# Pack_Disconnect_MOSFETs.net
KiCad netlist of a schematic drawn in Altium Designer
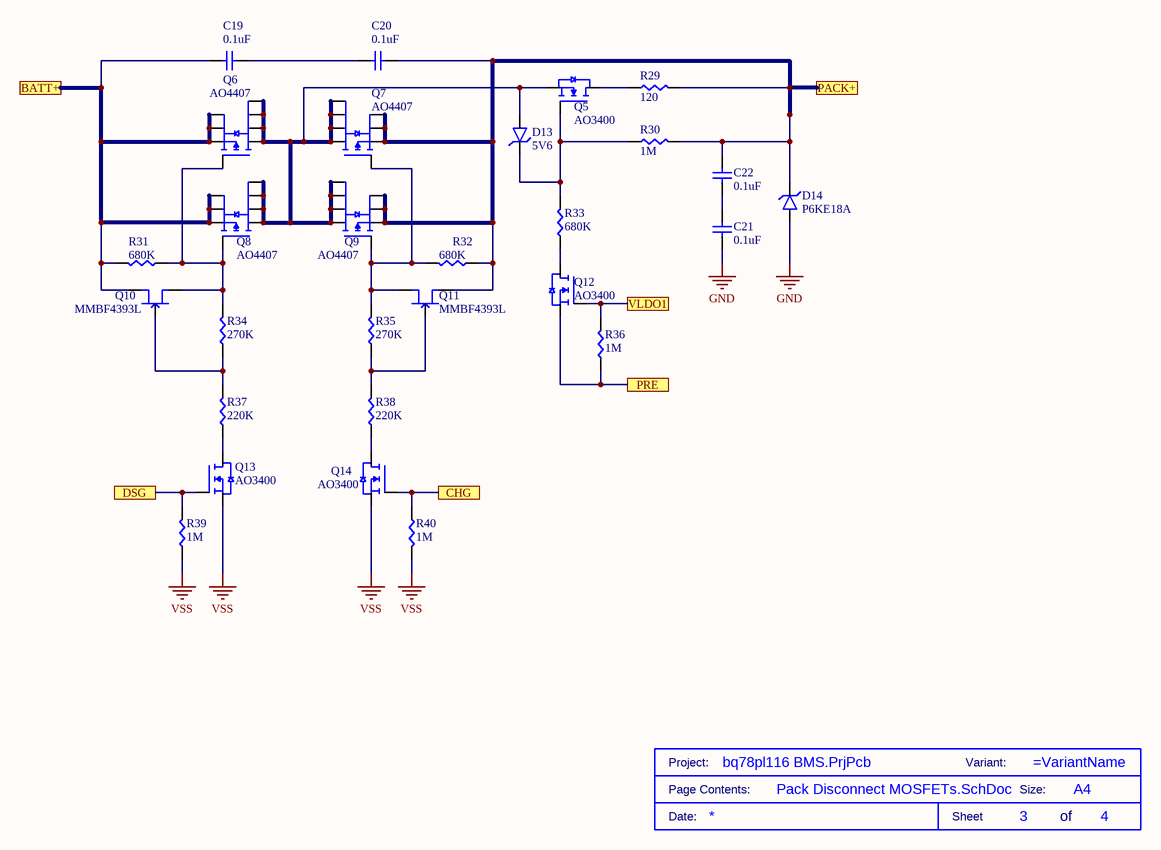
[diagram p0: Pack Disconnect MOSFETs.SchDoc]

(export (version "E")
  (design (tool "Eeschema 10.0.6"))
  (components
    (comp (ref "C19")
      (value "0.1uF")
      (footprint "C0805")
      (description "Cap Ceramic 0.1uF 50V X7R 10% SMD 0805 125°C Paper T/R")
      (fields
        (field (name "MANUFACTURER") "KEMET")
        (field (name "MANUFACTURER PART NUMBER") "C0805C104K5RAC7411")
      )
      (libsource (lib "MyLibrary") (part "CAP 0805 0.1uF"))
    )
    (comp (ref "C20")
      (value "0.1uF")
      (footprint "C0805")
      (description "Cap Ceramic 0.1uF 50V X7R 10% SMD 0805 125°C Paper T/R")
      (fields
        (field (name "MANUFACTURER") "KEMET")
        (field (name "MANUFACTURER PART NUMBER") "C0805C104K5RAC7411")
      )
      (libsource (lib "MyLibrary") (part "CAP 0805 0.1uF"))
    )
    (comp (ref "C21")
      (value "0.1uF")
      (footprint "C0805")
      (description "Cap Ceramic 0.1uF 50V X7R 10% SMD 0805 125°C Paper T/R")
      (fields
        (field (name "MANUFACTURER") "KEMET")
        (field (name "MANUFACTURER PART NUMBER") "C0805C104K5RAC7411")
      )
      (libsource (lib "MyLibrary") (part "CAP 0805 0.1uF"))
    )
    (comp (ref "C22")
      (value "0.1uF")
      (footprint "C0805")
      (description "Cap Ceramic 0.1uF 50V X7R 10% SMD 0805 125°C Paper T/R")
      (fields
        (field (name "MANUFACTURER") "KEMET")
        (field (name "MANUFACTURER PART NUMBER") "C0805C104K5RAC7411")
      )
      (libsource (lib "MyLibrary") (part "CAP 0805 0.1uF"))
    )
    (comp (ref "D13")
      (value "5V6")
      (footprint "MiniMELF")
      (description "Diode Zener Single 5.6V 7% 500mW Automotive 2-Pin Mini-MELF T/R")
      (fields (field (name "MANUFACTURER") "Diotec") (field (name "MANUFACTURER PART NUMBER") "ZMM5.6"))
      (libsource (lib "MyLibrary") (part "ZENER 5V6"))
    )
    (comp (ref "D14")
      (value "P6KE18A")
      (footprint "DO-15")
      (description "TVS DIODE 15.3VWM 32.5VC DO15")
      (fields (field (name "MANUFACTURER") "Littelfuse"))
      (libsource (lib "MyLibrary") (part "P6KE18A"))
    )
    (comp (ref "Q5")
      (value "AO3400")
      (footprint "SOT-23")
      (description "Trans MOSFET N-CH 30V 5.7A 3-Pin SOT-23")
      (fields
        (field (name "MANUFACTURER") "Alpha & Omega Semiconductor")
        (field (name "MANUFACTURER PART NUMBER") "AO3400A")
      )
      (libsource (lib "MyLibrary") (part "AO3400"))
    )
    (comp (ref "Q6")
      (value "AO4407")
      (footprint "SOIC-8")
      (description "MOSFET P-CH 30V 12A 8SOIC")
      (fields
        (field (name "MANUFACTURER") "Alpha & Omega Semiconductor")
        (field (name "MANUFACTURER PART NUMBER") "AO4407A")
      )
      (libsource (lib "MyLibrary") (part "AO4407"))
    )
    (comp (ref "Q7")
      (value "AO4407")
      (footprint "SOIC-8")
      (description "MOSFET P-CH 30V 12A 8SOIC")
      (fields
        (field (name "MANUFACTURER") "Alpha & Omega Semiconductor")
        (field (name "MANUFACTURER PART NUMBER") "AO4407A")
      )
      (libsource (lib "MyLibrary") (part "AO4407"))
    )
    (comp (ref "Q8")
      (value "AO4407")
      (footprint "SOIC-8")
      (description "MOSFET P-CH 30V 12A 8SOIC")
      (fields
        (field (name "MANUFACTURER") "Alpha & Omega Semiconductor")
        (field (name "MANUFACTURER PART NUMBER") "AO4407A")
      )
      (libsource (lib "MyLibrary") (part "AO4407"))
    )
    (comp (ref "Q9")
      (value "AO4407")
      (footprint "SOIC-8")
      (description "MOSFET P-CH 30V 12A 8SOIC")
      (fields
        (field (name "MANUFACTURER") "Alpha & Omega Semiconductor")
        (field (name "MANUFACTURER PART NUMBER") "AO4407A")
      )
      (libsource (lib "MyLibrary") (part "AO4407"))
    )
    (comp (ref "Q10")
      (value "MMBF4393L")
      (footprint "SOT-23")
      (description "Trans Jfet N-ch 30V 3-PIN SOT-23 T/r")
      (fields
        (field (name "MANUFACTURER") "ON Semiconductor")
        (field (name "MANUFACTURER PART NUMBER") "MMBF4393LT3G")
      )
      (libsource (lib "MyLibrary") (part "MMBF4393L"))
    )
    (comp (ref "Q11")
      (value "MMBF4393L")
      (footprint "SOT-23")
      (description "Trans Jfet N-ch 30V 3-PIN SOT-23 T/r")
      (fields
        (field (name "MANUFACTURER") "ON Semiconductor")
        (field (name "MANUFACTURER PART NUMBER") "MMBF4393LT3G")
      )
      (libsource (lib "MyLibrary") (part "MMBF4393L"))
    )
    (comp (ref "Q12")
      (value "AO3400")
      (footprint "SOT-23")
      (description "Trans MOSFET N-CH 30V 5.7A 3-Pin SOT-23")
      (fields
        (field (name "MANUFACTURER") "Alpha & Omega Semiconductor")
        (field (name "MANUFACTURER PART NUMBER") "AO3400A")
      )
      (libsource (lib "MyLibrary") (part "AO3400"))
    )
    (comp (ref "Q13")
      (value "AO3400")
      (footprint "SOT-23")
      (description "Trans MOSFET N-CH 30V 5.7A 3-Pin SOT-23")
      (fields
        (field (name "MANUFACTURER") "Alpha & Omega Semiconductor")
        (field (name "MANUFACTURER PART NUMBER") "AO3400A")
      )
      (libsource (lib "MyLibrary") (part "AO3400"))
    )
    (comp (ref "Q14")
      (value "AO3400")
      (footprint "SOT-23")
      (description "Trans MOSFET N-CH 30V 5.7A 3-Pin SOT-23")
      (fields
        (field (name "MANUFACTURER") "Alpha & Omega Semiconductor")
        (field (name "MANUFACTURER PART NUMBER") "AO3400A")
      )
      (libsource (lib "MyLibrary") (part "AO3400"))
    )
    (comp (ref "R29")
      (value "120")
      (footprint "RES TH 1W")
      (description "Ultra Miniature Style Metal Film Resistor 120Ohm 1W 5% Axial T/R")
      (fields
        (field (name "MANUFACTURER") "Yageo")
        (field (name "MANUFACTURER PART NUMBER") "FMP100JR-52-120R")
      )
      (libsource (lib "MyLibrary") (part "RES TH 120 1W"))
    )
    (comp (ref "R30")
      (value "1M")
      (footprint "R0805")
      (description "Res Thick Film 0805 1M Ohm 5% 0.125W(1/8W) ±200ppm/°C Pad SMD T/R")
      (fields
        (field (name "MANUFACTURER") "Vishay")
        (field (name "MANUFACTURER PART NUMBER") "CRCW08051M00JNEAC")
      )
      (libsource (lib "MyLibrary") (part "RES 0805 1M"))
    )
    (comp (ref "R31")
      (value "680K")
      (footprint "R0805")
      (description "Res Thick Film 0805 680K Ohm 5% 1/8W ±200ppm/°C Molded SMD SMD Paper T/R")
      (fields
        (field (name "MANUFACTURER") "Vishay Dale")
        (field (name "MANUFACTURER PART NUMBER") "CRCW0805680KJNEA")
      )
      (libsource (lib "MyLibrary") (part "RES 0805 680K"))
    )
    (comp (ref "R32")
      (value "680K")
      (footprint "R0805")
      (description "Res Thick Film 0805 680K Ohm 5% 1/8W ±200ppm/°C Molded SMD SMD Paper T/R")
      (fields
        (field (name "MANUFACTURER") "Vishay Dale")
        (field (name "MANUFACTURER PART NUMBER") "CRCW0805680KJNEA")
      )
      (libsource (lib "MyLibrary") (part "RES 0805 680K"))
    )
    (comp (ref "R33")
      (value "680K")
      (footprint "R0805")
      (description "Res Thick Film 0805 680K Ohm 5% 1/8W ±200ppm/°C Molded SMD SMD Paper T/R")
      (fields
        (field (name "MANUFACTURER") "Vishay Dale")
        (field (name "MANUFACTURER PART NUMBER") "CRCW0805680KJNEA")
      )
      (libsource (lib "MyLibrary") (part "RES 0805 680K"))
    )
    (comp (ref "R34")
      (value "270K")
      (footprint "R0805")
      (description "Res Thick Film 0805 270K Ohm 5% 1/8W ±200ppm/°C Molded SMD SMD Paper T/R")
      (fields
        (field (name "MANUFACTURER") "Vishay Dale")
        (field (name "MANUFACTURER PART NUMBER") "CRCW0805270KJNEA")
      )
      (libsource (lib "MyLibrary") (part "RES 0805 270K"))
    )
    (comp (ref "R35")
      (value "270K")
      (footprint "R0805")
      (description "Res Thick Film 0805 270K Ohm 5% 1/8W ±200ppm/°C Molded SMD SMD Paper T/R")
      (fields
        (field (name "MANUFACTURER") "Vishay Dale")
        (field (name "MANUFACTURER PART NUMBER") "CRCW0805270KJNEA")
      )
      (libsource (lib "MyLibrary") (part "RES 0805 270K"))
    )
    (comp (ref "R36")
      (value "1M")
      (footprint "R0805")
      (description "Res Thick Film 0805 1M Ohm 5% 0.125W(1/8W) ±200ppm/°C Pad SMD T/R")
      (fields
        (field (name "MANUFACTURER") "Vishay")
        (field (name "MANUFACTURER PART NUMBER") "CRCW08051M00JNEAC")
      )
      (libsource (lib "MyLibrary") (part "RES 0805 1M"))
    )
    (comp (ref "R37")
      (value "220K")
      (footprint "R0805")
      (description "Res Thick Film 0805 220K Ohm 5% 1/8W ±200ppm/°C Molded SMD SMD Paper T/R")
      (fields
        (field (name "MANUFACTURER") "Vishay Dale")
        (field (name "MANUFACTURER PART NUMBER") "CRCW0805220KJNEA")
      )
      (libsource (lib "MyLibrary") (part "RES 0805 220K"))
    )
    (comp (ref "R38")
      (value "220K")
      (footprint "R0805")
      (description "Res Thick Film 0805 220K Ohm 5% 1/8W ±200ppm/°C Molded SMD SMD Paper T/R")
      (fields
        (field (name "MANUFACTURER") "Vishay Dale")
        (field (name "MANUFACTURER PART NUMBER") "CRCW0805220KJNEA")
      )
      (libsource (lib "MyLibrary") (part "RES 0805 220K"))
    )
    (comp (ref "R39")
      (value "1M")
      (footprint "R0805")
      (description "Res Thick Film 0805 1M Ohm 5% 0.125W(1/8W) ±200ppm/°C Pad SMD T/R")
      (fields
        (field (name "MANUFACTURER") "Vishay")
        (field (name "MANUFACTURER PART NUMBER") "CRCW08051M00JNEAC")
      )
      (libsource (lib "MyLibrary") (part "RES 0805 1M"))
    )
    (comp (ref "R40")
      (value "1M")
      (footprint "R0805")
      (description "Res Thick Film 0805 1M Ohm 5% 0.125W(1/8W) ±200ppm/°C Pad SMD T/R")
      (fields
        (field (name "MANUFACTURER") "Vishay")
        (field (name "MANUFACTURER PART NUMBER") "CRCW08051M00JNEAC")
      )
      (libsource (lib "MyLibrary") (part "RES 0805 1M"))
    )
  )
  (nets
    (net (code "1") (name "/BATT+") (class "Default")
      (node (ref "C19") (pin "1") (pinfunction "1_1") (pintype "passive"))
      (node (ref "Q10") (pin "1") (pinfunction "D_1") (pintype "passive"))
      (node (ref "Q6") (pin "1") (pinfunction "S_1") (pintype "passive"))
      (node (ref "Q6") (pin "2") (pinfunction "S_2") (pintype "passive"))
      (node (ref "Q6") (pin "3") (pinfunction "S_3") (pintype "passive"))
      (node (ref "Q8") (pin "1") (pinfunction "S_1") (pintype "passive"))
      (node (ref "Q8") (pin "2") (pinfunction "S_2") (pintype "passive"))
      (node (ref "Q8") (pin "3") (pinfunction "S_3") (pintype "passive"))
      (node (ref "R31") (pin "2") (pinfunction "2_2") (pintype "passive"))
    )
    (net (code "2") (name "/CHG") (class "Default")
      (node (ref "Q14") (pin "1") (pinfunction "G_1") (pintype "passive"))
      (node (ref "R40") (pin "2") (pinfunction "2_2") (pintype "passive"))
    )
    (net (code "3") (name "/DSG") (class "Default")
      (node (ref "Q13") (pin "1") (pinfunction "G_1") (pintype "passive"))
      (node (ref "R39") (pin "2") (pinfunction "2_2") (pintype "passive"))
    )
    (net (code "4") (name "/PACK+") (class "Default")
      (node (ref "C20") (pin "2") (pinfunction "2_2") (pintype "passive"))
      (node (ref "C22") (pin "1") (pinfunction "1_1") (pintype "passive"))
      (node (ref "D14") (pin "2") (pinfunction "K_2") (pintype "passive"))
      (node (ref "Q11") (pin "1") (pinfunction "D_1") (pintype "passive"))
      (node (ref "Q7") (pin "1") (pinfunction "S_1") (pintype "passive"))
      (node (ref "Q7") (pin "2") (pinfunction "S_2") (pintype "passive"))
      (node (ref "Q7") (pin "3") (pinfunction "S_3") (pintype "passive"))
      (node (ref "Q9") (pin "1") (pinfunction "S_1") (pintype "passive"))
      (node (ref "Q9") (pin "2") (pinfunction "S_2") (pintype "passive"))
      (node (ref "Q9") (pin "3") (pinfunction "S_3") (pintype "passive"))
      (node (ref "R29") (pin "2") (pinfunction "2_2") (pintype "passive"))
      (node (ref "R30") (pin "2") (pinfunction "2_2") (pintype "passive"))
      (node (ref "R32") (pin "1") (pinfunction "1_1") (pintype "passive"))
    )
    (net (code "5") (name "/PRE") (class "Default")
      (node (ref "Q12") (pin "2") (pinfunction "S_2") (pintype "passive"))
      (node (ref "R36") (pin "1") (pinfunction "1_1") (pintype "passive"))
    )
    (net (code "6") (name "/VLDO1") (class "Default")
      (node (ref "Q12") (pin "1") (pinfunction "G_1") (pintype "passive"))
      (node (ref "R36") (pin "2") (pinfunction "2_2") (pintype "passive"))
    )
    (net (code "7") (name "GND") (class "Default")
      (node (ref "C21") (pin "2") (pinfunction "2_2") (pintype "passive"))
      (node (ref "D14") (pin "1") (pinfunction "A_1") (pintype "passive"))
    )
    (net (code "8") (name "Net-(C19-Pad2)") (class "Default")
      (node (ref "C19") (pin "2") (pinfunction "2_2") (pintype "passive"))
      (node (ref "C20") (pin "1") (pinfunction "1_1") (pintype "passive"))
    )
    (net (code "9") (name "Net-(C21-Pad1)") (class "Default")
      (node (ref "C21") (pin "1") (pinfunction "1_1") (pintype "passive"))
      (node (ref "C22") (pin "2") (pinfunction "2_2") (pintype "passive"))
    )
    (net (code "10") (name "Net-(D13-A)") (class "Default")
      (node (ref "D13") (pin "1") (pinfunction "A_1") (pintype "passive"))
      (node (ref "Q5") (pin "2") (pinfunction "S_2") (pintype "passive"))
      (node (ref "Q6") (pin "5") (pinfunction "D_5") (pintype "passive"))
      (node (ref "Q6") (pin "6") (pinfunction "D_6") (pintype "passive"))
      (node (ref "Q6") (pin "7") (pinfunction "D_7") (pintype "passive"))
      (node (ref "Q6") (pin "8") (pinfunction "D_8") (pintype "passive"))
      (node (ref "Q7") (pin "5") (pinfunction "D_5") (pintype "passive"))
      (node (ref "Q7") (pin "6") (pinfunction "D_6") (pintype "passive"))
      (node (ref "Q7") (pin "7") (pinfunction "D_7") (pintype "passive"))
      (node (ref "Q7") (pin "8") (pinfunction "D_8") (pintype "passive"))
      (node (ref "Q8") (pin "5") (pinfunction "D_5") (pintype "passive"))
      (node (ref "Q8") (pin "6") (pinfunction "D_6") (pintype "passive"))
      (node (ref "Q8") (pin "7") (pinfunction "D_7") (pintype "passive"))
      (node (ref "Q8") (pin "8") (pinfunction "D_8") (pintype "passive"))
      (node (ref "Q9") (pin "5") (pinfunction "D_5") (pintype "passive"))
      (node (ref "Q9") (pin "6") (pinfunction "D_6") (pintype "passive"))
      (node (ref "Q9") (pin "7") (pinfunction "D_7") (pintype "passive"))
      (node (ref "Q9") (pin "8") (pinfunction "D_8") (pintype "passive"))
    )
    (net (code "11") (name "Net-(D13-K)") (class "Default")
      (node (ref "D13") (pin "2") (pinfunction "K_2") (pintype "passive"))
      (node (ref "Q5") (pin "1") (pinfunction "G_1") (pintype "passive"))
      (node (ref "R30") (pin "1") (pinfunction "1_1") (pintype "passive"))
      (node (ref "R33") (pin "2") (pinfunction "2_2") (pintype "passive"))
    )
    (net (code "12") (name "Net-(Q5-D)") (class "Default")
      (node (ref "Q5") (pin "3") (pinfunction "D_3") (pintype "passive"))
      (node (ref "R29") (pin "1") (pinfunction "1_1") (pintype "passive"))
    )
    (net (code "13") (name "Net-(Q10-G)") (class "Default")
      (node (ref "Q10") (pin "3") (pinfunction "G_3") (pintype "passive"))
      (node (ref "R34") (pin "1") (pinfunction "1_1") (pintype "passive"))
      (node (ref "R37") (pin "2") (pinfunction "2_2") (pintype "passive"))
    )
    (net (code "14") (name "Net-(Q10-S)") (class "Default")
      (node (ref "Q10") (pin "2") (pinfunction "S_2") (pintype "passive"))
      (node (ref "Q6") (pin "4") (pinfunction "G_4") (pintype "passive"))
      (node (ref "Q8") (pin "4") (pinfunction "G_4") (pintype "passive"))
      (node (ref "R31") (pin "1") (pinfunction "1_1") (pintype "passive"))
      (node (ref "R34") (pin "2") (pinfunction "2_2") (pintype "passive"))
    )
    (net (code "15") (name "Net-(Q11-G)") (class "Default")
      (node (ref "Q11") (pin "3") (pinfunction "G_3") (pintype "passive"))
      (node (ref "R35") (pin "1") (pinfunction "1_1") (pintype "passive"))
      (node (ref "R38") (pin "2") (pinfunction "2_2") (pintype "passive"))
    )
    (net (code "16") (name "Net-(Q11-S)") (class "Default")
      (node (ref "Q11") (pin "2") (pinfunction "S_2") (pintype "passive"))
      (node (ref "Q7") (pin "4") (pinfunction "G_4") (pintype "passive"))
      (node (ref "Q9") (pin "4") (pinfunction "G_4") (pintype "passive"))
      (node (ref "R32") (pin "2") (pinfunction "2_2") (pintype "passive"))
      (node (ref "R35") (pin "2") (pinfunction "2_2") (pintype "passive"))
    )
    (net (code "17") (name "Net-(Q12-D)") (class "Default")
      (node (ref "Q12") (pin "3") (pinfunction "D_3") (pintype "passive"))
      (node (ref "R33") (pin "1") (pinfunction "1_1") (pintype "passive"))
    )
    (net (code "18") (name "Net-(Q13-D)") (class "Default")
      (node (ref "Q13") (pin "3") (pinfunction "D_3") (pintype "passive"))
      (node (ref "R37") (pin "1") (pinfunction "1_1") (pintype "passive"))
    )
    (net (code "19") (name "Net-(Q14-D)") (class "Default")
      (node (ref "Q14") (pin "3") (pinfunction "D_3") (pintype "passive"))
      (node (ref "R38") (pin "1") (pinfunction "1_1") (pintype "passive"))
    )
    (net (code "20") (name "VSS") (class "Default")
      (node (ref "Q13") (pin "2") (pinfunction "S_2") (pintype "passive"))
      (node (ref "Q14") (pin "2") (pinfunction "S_2") (pintype "passive"))
      (node (ref "R39") (pin "1") (pinfunction "1_1") (pintype "passive"))
      (node (ref "R40") (pin "1") (pinfunction "1_1") (pintype "passive"))
    )
  )
)
